# jlink_to_tag.net
KiCad netlist of a schematic drawn in EAGLE
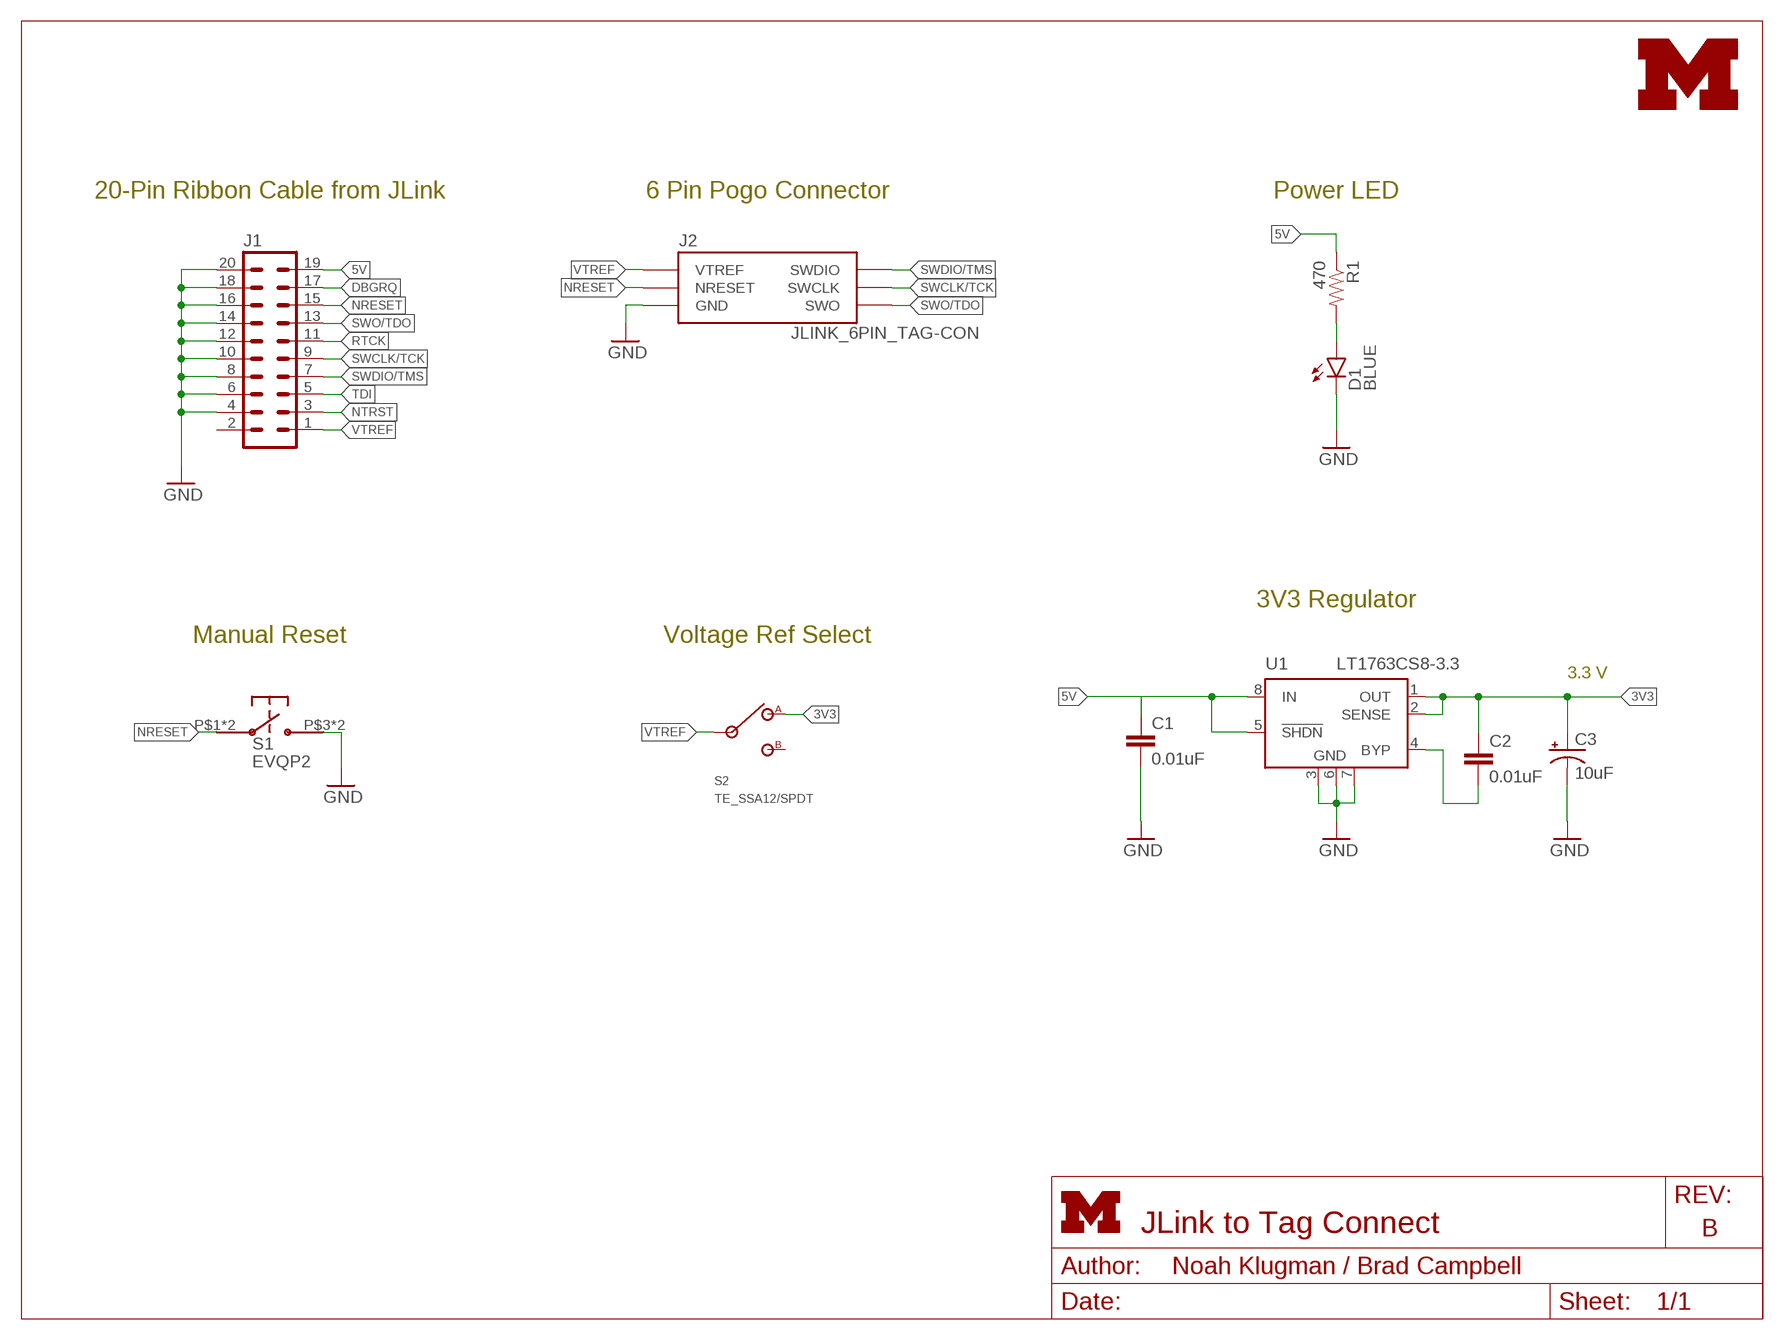
[diagram p0: schematic, sheet 1]

(export (version "E")
  (design (tool "Eeschema 10.0.6"))
  (components
    (comp (ref "C1")
      (value "0.01uF")
      (footprint "eagle-import:C0603")
      (libsource (lib "eagle-import") (part "C-EUC0603"))
    )
    (comp (ref "C2")
      (value "0.01uF")
      (footprint "eagle-import:C0603")
      (libsource (lib "eagle-import") (part "C-EUC0603"))
    )
    (comp (ref "C3")
      (value "10uF")
      (footprint "eagle-import:EIA3216")
      (libsource (lib "eagle-import") (part "CAP_POL1206"))
    )
    (comp (ref "D1")
      (value "BLUE")
      (footprint "eagle-import:LED-0603")
      (libsource (lib "eagle-import") (part "LED-BLUE0603"))
    )
    (comp (ref "J1")
      (value "ML20")
      (footprint "eagle-import:ML20")
      (libsource (lib "eagle-import") (part "ML20"))
    )
    (comp (ref "J2")
      (value "JLINK_6PIN_TAG-CON")
      (footprint "eagle-import:2X3_MALE_SHROUDED_0.100")
      (libsource (lib "eagle-import") (part "JLINK_6PIN_TAG-CON"))
    )
    (comp (ref "LOGO1")
      (value "UMICH_SOLID_SMALL+")
      (footprint "eagle-import:UMICH_SOLID_100MIL")
      (libsource (lib "eagle-import") (part "UMICH_SOLID_SMALL+"))
    )
    (comp (ref "R1")
      (value "470")
      (footprint "eagle-import:0603-RES")
      (libsource (lib "eagle-import") (part "RESISTOR0603-RES"))
    )
    (comp (ref "S1")
      (value "EVQP2")
      (footprint "eagle-import:EVQP2")
      (libsource (lib "eagle-import") (part "EVQP2"))
    )
    (comp (ref "S2")
      (value "TE_SSA12/SPDT")
      (footprint "eagle-import:TE_SSA12_SPDT")
      (libsource (lib "eagle-import") (part "TE_SSA12/SPDT"))
    )
    (comp (ref "U1")
      (value "LT1763CS8-3.3")
      (footprint "eagle-import:SOIC8")
      (libsource (lib "eagle-import") (part "LT1763CS8-3.3"))
    )
  )
  (nets
    (net (code "1") (name "3V3") (class "Default")
      (node (ref "C2") (pin "1") (pinfunction "1_1") (pintype "passive"))
      (node (ref "C3") (pin "A") (pinfunction "+_A") (pintype "passive"))
      (node (ref "S2") (pin "1") (pinfunction "A_1") (pintype "bidirectional"))
      (node (ref "U1") (pin "1") (pinfunction "OUT_1") (pintype "passive"))
      (node (ref "U1") (pin "2") (pinfunction "SENSE_2") (pintype "input"))
    )
    (net (code "2") (name "5V") (class "Default")
      (node (ref "C1") (pin "1") (pinfunction "1_1") (pintype "passive"))
      (node (ref "J1") (pin "19") (pinfunction "19_19") (pintype "passive"))
      (node (ref "R1") (pin "1") (pinfunction "1_1") (pintype "passive"))
      (node (ref "U1") (pin "5") (pinfunction "~{SHDN}_5") (pintype "input"))
      (node (ref "U1") (pin "8") (pinfunction "IN_8") (pintype "input"))
    )
    (net (code "3") (name "DBGRQ") (class "Default")
      (node (ref "J1") (pin "17") (pinfunction "17_17") (pintype "passive"))
    )
    (net (code "4") (name "GND") (class "Default")
      (node (ref "C1") (pin "2") (pinfunction "2_2") (pintype "passive"))
      (node (ref "C3") (pin "C") (pinfunction "-_C") (pintype "passive"))
      (node (ref "D1") (pin "C") (pinfunction "C_C") (pintype "passive"))
      (node (ref "J1") (pin "10") (pinfunction "10_10") (pintype "passive"))
      (node (ref "J1") (pin "12") (pinfunction "12_12") (pintype "passive"))
      (node (ref "J1") (pin "14") (pinfunction "14_14") (pintype "passive"))
      (node (ref "J1") (pin "16") (pinfunction "16_16") (pintype "passive"))
      (node (ref "J1") (pin "18") (pinfunction "18_18") (pintype "passive"))
      (node (ref "J1") (pin "20") (pinfunction "20_20") (pintype "passive"))
      (node (ref "J1") (pin "4") (pinfunction "4_4") (pintype "passive"))
      (node (ref "J1") (pin "6") (pinfunction "6_6") (pintype "passive"))
      (node (ref "J1") (pin "8") (pinfunction "8_8") (pintype "passive"))
      (node (ref "J2") (pin "5") (pinfunction "GND_5") (pintype "bidirectional"))
      (node (ref "S1") (pin "P$3") (pinfunction "P$2_P$3") (pintype "passive"))
      (node (ref "S1") (pin "P$4") (pinfunction "P$2_P$4") (pintype "passive"))
      (node (ref "U1") (pin "3") (pinfunction "GND_3") (pintype "power_in"))
      (node (ref "U1") (pin "6") (pinfunction "GND_6") (pintype "power_in"))
      (node (ref "U1") (pin "7") (pinfunction "GND_7") (pintype "power_in"))
    )
    (net (code "5") (name "NRESET") (class "Default")
      (node (ref "J1") (pin "15") (pinfunction "15_15") (pintype "passive"))
      (node (ref "J2") (pin "3") (pinfunction "NRESET_3") (pintype "bidirectional"))
      (node (ref "S1") (pin "P$1") (pinfunction "P$1_P$1") (pintype "passive"))
      (node (ref "S1") (pin "P$2") (pinfunction "P$1_P$2") (pintype "passive"))
    )
    (net (code "6") (name "NTRST") (class "Default")
      (node (ref "J1") (pin "3") (pinfunction "3_3") (pintype "passive"))
    )
    (net (code "7") (name "Net-(D1-PadA)") (class "Default")
      (node (ref "D1") (pin "A") (pinfunction "A_A") (pintype "passive"))
      (node (ref "R1") (pin "2") (pinfunction "2_2") (pintype "passive"))
    )
    (net (code "8") (name "Net-(U1-BYP)") (class "Default")
      (node (ref "C2") (pin "2") (pinfunction "2_2") (pintype "passive"))
      (node (ref "U1") (pin "4") (pinfunction "BYP_4") (pintype "input"))
    )
    (net (code "9") (name "RTCK") (class "Default")
      (node (ref "J1") (pin "11") (pinfunction "11_11") (pintype "passive"))
    )
    (net (code "10") (name "SWCLK{slash}TCK") (class "Default")
      (node (ref "J1") (pin "9") (pinfunction "9_9") (pintype "passive"))
      (node (ref "J2") (pin "4") (pinfunction "SWCLK_4") (pintype "bidirectional"))
    )
    (net (code "11") (name "SWDIO{slash}TMS") (class "Default")
      (node (ref "J1") (pin "7") (pinfunction "7_7") (pintype "passive"))
      (node (ref "J2") (pin "2") (pinfunction "SWDIO_2") (pintype "bidirectional"))
    )
    (net (code "12") (name "SWO{slash}TDO") (class "Default")
      (node (ref "J1") (pin "13") (pinfunction "13_13") (pintype "passive"))
      (node (ref "J2") (pin "6") (pinfunction "SWO_6") (pintype "bidirectional"))
    )
    (net (code "13") (name "TDI") (class "Default")
      (node (ref "J1") (pin "5") (pinfunction "5_5") (pintype "passive"))
    )
    (net (code "14") (name "VTREF") (class "Default")
      (node (ref "J1") (pin "1") (pinfunction "1_1") (pintype "passive"))
      (node (ref "J2") (pin "1") (pinfunction "VTREF_1") (pintype "bidirectional"))
      (node (ref "S2") (pin "IN") (pinfunction "IN_IN") (pintype "bidirectional"))
    )
    (net (code "15") (name "unconnected-(J1-Pad2)") (class "Default")
      (node (ref "J1") (pin "2") (pinfunction "2_2") (pintype "passive"))
    )
    (net (code "16") (name "unconnected-(S2-B-Pad2)") (class "Default")
      (node (ref "S2") (pin "2") (pinfunction "B_2") (pintype "bidirectional"))
    )
  )
)
